# Power_Regulation.net
KiCad netlist of a schematic drawn in Altium Designer
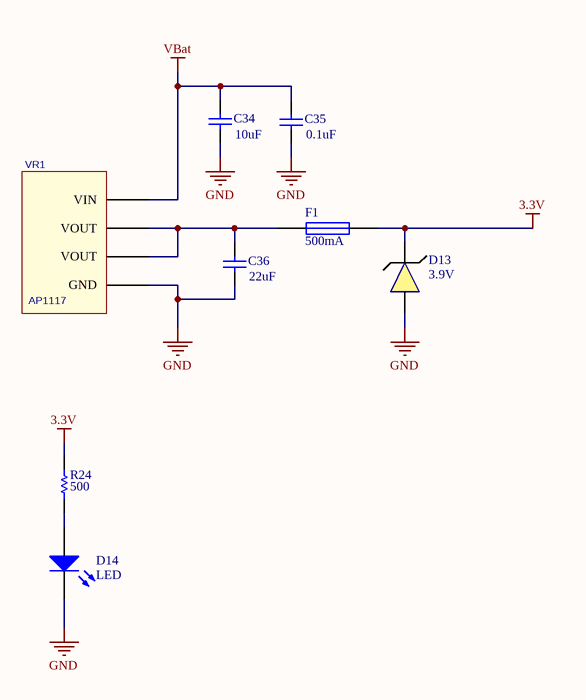
[diagram p0: Power_Regulation.SchDoc]

(export (version "E")
  (design (tool "Eeschema 10.0.6"))
  (components
    (comp (ref "C34")
      (value "10uF")
      (footprint "1608[0603]")
      (description "Capacitor (Semiconductor SIM Model)")
      (fields (field (name "Comment") "Cap Semi") (field (name "PUBLISHER") "Altium Limited"))
      (libsource (lib "Miscellaneous Devices") (part "Cap Semi"))
    )
    (comp (ref "C35")
      (value "0.1uF")
      (footprint "1608[0603]")
      (description "Capacitor (Semiconductor SIM Model)")
      (fields (field (name "Comment") "Cap Semi") (field (name "PUBLISHER") "Altium Limited"))
      (libsource (lib "Miscellaneous Devices") (part "Cap Semi"))
    )
    (comp (ref "C36")
      (value "22uF")
      (footprint "1608[0603]")
      (description "Capacitor (Semiconductor SIM Model)")
      (fields (field (name "Comment") "Cap Semi") (field (name "PUBLISHER") "Altium Limited"))
      (libsource (lib "Miscellaneous Devices") (part "Cap Semi"))
    )
    (comp (ref "D13")
      (value "3.9V")
      (footprint "DO-214AC")
      (description "3.9V 1.25W")
      (libsource (lib "diodes") (part "Zener Diode"))
    )
    (comp (ref "D14")
      (value "LED")
      (footprint "0603")
      (fields
        (field (name "VENDOR PART NUMBER") "751-1203-ND")
        (field (name "MANUFACTURER") "Vishay")
        (field (name "MANUFACTURER PART NUMBER") "TSAL6100")
        (field (name "PUBLISHER") "Anthony Merlino")
      )
      (libsource (lib "passives") (part "LED"))
    )
    (comp (ref "F1")
      (value "500mA")
      (footprint "0603 PTC Fuse")
      (description "Fuse")
      (fields (field (name "PUBLISHER") "Altium Limited"))
      (libsource (lib "passives") (part "Fuse"))
    )
    (comp (ref "R24")
      (value "500")
      (footprint "0603")
      (description "Resistor")
      (fields (field (name "PUBLISHER") "Altium Limited"))
      (libsource (lib "passives") (part "Resistor"))
    )
    (comp (ref "VR1") (value "AP1117") (footprint "SOT-223") (libsource (lib "Devices") (part "AP1117")))
  )
  (nets
    (net (code "1") (name "3.3V") (class "Default")
      (node (ref "D13") (pin "1") (pintype "passive"))
      (node (ref "F1") (pin "2") (pinfunction "2_2") (pintype "passive"))
      (node (ref "R24") (pin "2") (pinfunction "2_2") (pintype "passive"))
    )
    (net (code "2") (name "GND") (class "Default")
      (node (ref "C34") (pin "1") (pinfunction "1_1") (pintype "passive"))
      (node (ref "C35") (pin "1") (pinfunction "1_1") (pintype "passive"))
      (node (ref "C36") (pin "1") (pinfunction "1_1") (pintype "passive"))
      (node (ref "D13") (pin "2") (pintype "passive"))
      (node (ref "D14") (pin "2") (pinfunction "K_2") (pintype "passive"))
      (node (ref "VR1") (pin "1") (pinfunction "GND_1") (pintype "passive"))
    )
    (net (code "3") (name "Net-(C36-Pad2)") (class "Default")
      (node (ref "C36") (pin "2") (pinfunction "2_2") (pintype "passive"))
      (node (ref "F1") (pin "1") (pinfunction "1_1") (pintype "passive"))
      (node (ref "VR1") (pin "2") (pinfunction "VOUT_2") (pintype "passive"))
      (node (ref "VR1") (pin "4") (pinfunction "VOUT_4") (pintype "passive"))
    )
    (net (code "4") (name "Net-(D14-A)") (class "Default")
      (node (ref "D14") (pin "1") (pinfunction "A_1") (pintype "passive"))
      (node (ref "R24") (pin "1") (pinfunction "1_1") (pintype "passive"))
    )
    (net (code "5") (name "VBat") (class "Default")
      (node (ref "C34") (pin "2") (pinfunction "2_2") (pintype "passive"))
      (node (ref "C35") (pin "2") (pinfunction "2_2") (pintype "passive"))
      (node (ref "VR1") (pin "3") (pinfunction "VIN_3") (pintype "passive"))
    )
  )
)
